# 52_Alimentacion.net
KiCad netlist of a schematic drawn in Altium Designer
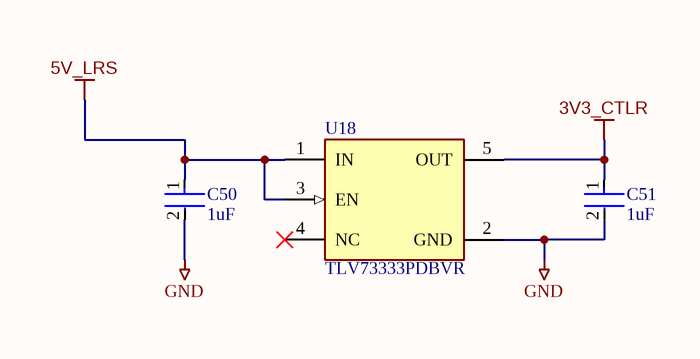
[diagram p0: 52_Alimentacion.SchDoc]

(export (version "E")
  (design (tool "Eeschema 10.0.6"))
  (components
    (comp (ref "C50")
      (value "1uF")
      (footprint "FP-C0402C-BB-IPC_B")
      (description "CAP CER 1UF 16V X5R 0402")
      (fields (field (name "TOLERANCE") "10%"))
      (libsource (lib "Altium Content Vault") (part "b4654b650e69147ec39a6b967a45e02"))
    )
    (comp (ref "C51")
      (value "1uF")
      (footprint "FP-C0402C-BB-IPC_B")
      (description "CAP CER 1UF 16V X5R 0402")
      (fields (field (name "TOLERANCE") "10%"))
      (libsource (lib "Altium Content Vault") (part "b4654b650e69147ec39a6b967a45e02"))
    )
    (comp (ref "U18")
      (value "TLV73333PDBVR")
      (footprint "FP-DBV0005A-MFG")
      (description "IC REG LINEAR 3.3V 300MA SOT23-5")
      (fields
        (field (name "MANUFACTURER") "Texas Instruments")
        (field (name "OCTOPART") "https://octopart.com/tlv73333pdbvr-texas+instruments-51080890")
      )
      (libsource (lib "Altium Content Vault") (part "10cdd6a861ce8db355dac0efc8b397e"))
    )
  )
  (nets
    (net (code "1") (name "3V3_CTLR") (class "Default")
      (node (ref "C51") (pin "1") (pinfunction "1_1") (pintype "passive"))
      (node (ref "U18") (pin "5") (pinfunction "OUT_5") (pintype "power_in"))
    )
    (net (code "2") (name "5V_LRS") (class "Default")
      (node (ref "C50") (pin "1") (pinfunction "1_1") (pintype "passive"))
      (node (ref "U18") (pin "1") (pinfunction "IN_1") (pintype "power_in"))
      (node (ref "U18") (pin "3") (pinfunction "EN_3") (pintype "input"))
    )
    (net (code "3") (name "GND") (class "Default")
      (node (ref "C50") (pin "2") (pinfunction "2_2") (pintype "passive"))
      (node (ref "C51") (pin "2") (pinfunction "2_2") (pintype "passive"))
      (node (ref "U18") (pin "2") (pinfunction "GND_2") (pintype "power_in"))
    )
    (net (code "4") (name "unconnected-(U18-NC-Pad4)") (class "Default")
      (node (ref "U18") (pin "4") (pinfunction "NC_4") (pintype "passive+no_connect"))
    )
  )
)
